# 5MMLedBreakoutForArduino.net
KiCad netlist of a schematic drawn in EAGLE
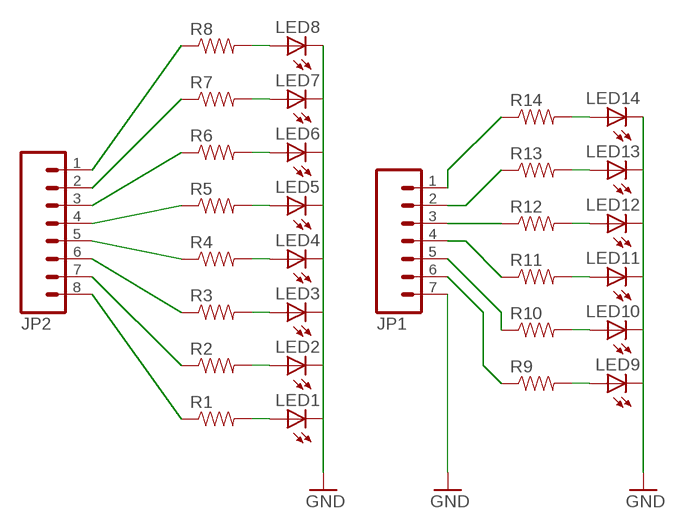
[diagram p0: schematic, sheet 1]

(export (version "E")
  (design (tool "Eeschema 10.0.6"))
  (components
    (comp (ref "JP1")
      (value "M07")
      (footprint "eagle-import:1X07")
      (libsource (lib "eagle-import") (part "M07"))
    )
    (comp (ref "JP2")
      (value "M081X08")
      (footprint "eagle-import:1X08")
      (libsource (lib "eagle-import") (part "M081X08"))
    )
    (comp (ref "LED1")
      (value "LED5MM")
      (footprint "eagle-import:LED5MM")
      (libsource (lib "eagle-import") (part "LED5MM"))
    )
    (comp (ref "LED2")
      (value "LED5MM")
      (footprint "eagle-import:LED5MM")
      (libsource (lib "eagle-import") (part "LED5MM"))
    )
    (comp (ref "LED3")
      (value "LED5MM")
      (footprint "eagle-import:LED5MM")
      (libsource (lib "eagle-import") (part "LED5MM"))
    )
    (comp (ref "LED4")
      (value "LED5MM")
      (footprint "eagle-import:LED5MM")
      (libsource (lib "eagle-import") (part "LED5MM"))
    )
    (comp (ref "LED5")
      (value "LED5MM")
      (footprint "eagle-import:LED5MM")
      (libsource (lib "eagle-import") (part "LED5MM"))
    )
    (comp (ref "LED6")
      (value "LED5MM")
      (footprint "eagle-import:LED5MM")
      (libsource (lib "eagle-import") (part "LED5MM"))
    )
    (comp (ref "LED7")
      (value "LED5MM")
      (footprint "eagle-import:LED5MM")
      (libsource (lib "eagle-import") (part "LED5MM"))
    )
    (comp (ref "LED8")
      (value "LED5MM")
      (footprint "eagle-import:LED5MM")
      (libsource (lib "eagle-import") (part "LED5MM"))
    )
    (comp (ref "LED9")
      (value "LED5MM")
      (footprint "eagle-import:LED5MM")
      (libsource (lib "eagle-import") (part "LED5MM"))
    )
    (comp (ref "LED10")
      (value "LED5MM")
      (footprint "eagle-import:LED5MM")
      (libsource (lib "eagle-import") (part "LED5MM"))
    )
    (comp (ref "LED11")
      (value "LED5MM")
      (footprint "eagle-import:LED5MM")
      (libsource (lib "eagle-import") (part "LED5MM"))
    )
    (comp (ref "LED12")
      (value "LED5MM")
      (footprint "eagle-import:LED5MM")
      (libsource (lib "eagle-import") (part "LED5MM"))
    )
    (comp (ref "LED13")
      (value "LED5MM")
      (footprint "eagle-import:LED5MM")
      (libsource (lib "eagle-import") (part "LED5MM"))
    )
    (comp (ref "LED14")
      (value "LED5MM")
      (footprint "eagle-import:LED5MM")
      (libsource (lib "eagle-import") (part "LED5MM"))
    )
    (comp (ref "R1")
      (value "RESISTORAXIAL-0.3")
      (footprint "eagle-import:AXIAL-0.3")
      (libsource (lib "eagle-import") (part "RESISTORAXIAL-0.3"))
    )
    (comp (ref "R2")
      (value "RESISTORAXIAL-0.3")
      (footprint "eagle-import:AXIAL-0.3")
      (libsource (lib "eagle-import") (part "RESISTORAXIAL-0.3"))
    )
    (comp (ref "R3")
      (value "RESISTORAXIAL-0.3")
      (footprint "eagle-import:AXIAL-0.3")
      (libsource (lib "eagle-import") (part "RESISTORAXIAL-0.3"))
    )
    (comp (ref "R4")
      (value "RESISTORAXIAL-0.3")
      (footprint "eagle-import:AXIAL-0.3")
      (libsource (lib "eagle-import") (part "RESISTORAXIAL-0.3"))
    )
    (comp (ref "R5")
      (value "RESISTORAXIAL-0.3")
      (footprint "eagle-import:AXIAL-0.3")
      (libsource (lib "eagle-import") (part "RESISTORAXIAL-0.3"))
    )
    (comp (ref "R6")
      (value "RESISTORAXIAL-0.3")
      (footprint "eagle-import:AXIAL-0.3")
      (libsource (lib "eagle-import") (part "RESISTORAXIAL-0.3"))
    )
    (comp (ref "R7")
      (value "RESISTORAXIAL-0.3")
      (footprint "eagle-import:AXIAL-0.3")
      (libsource (lib "eagle-import") (part "RESISTORAXIAL-0.3"))
    )
    (comp (ref "R8")
      (value "RESISTORAXIAL-0.3")
      (footprint "eagle-import:AXIAL-0.3")
      (libsource (lib "eagle-import") (part "RESISTORAXIAL-0.3"))
    )
    (comp (ref "R9")
      (value "RESISTORAXIAL-0.3")
      (footprint "eagle-import:AXIAL-0.3")
      (libsource (lib "eagle-import") (part "RESISTORAXIAL-0.3"))
    )
    (comp (ref "R10")
      (value "RESISTORAXIAL-0.3")
      (footprint "eagle-import:AXIAL-0.3")
      (libsource (lib "eagle-import") (part "RESISTORAXIAL-0.3"))
    )
    (comp (ref "R11")
      (value "RESISTORAXIAL-0.3")
      (footprint "eagle-import:AXIAL-0.3")
      (libsource (lib "eagle-import") (part "RESISTORAXIAL-0.3"))
    )
    (comp (ref "R12")
      (value "RESISTORAXIAL-0.3")
      (footprint "eagle-import:AXIAL-0.3")
      (libsource (lib "eagle-import") (part "RESISTORAXIAL-0.3"))
    )
    (comp (ref "R13")
      (value "RESISTORAXIAL-0.3")
      (footprint "eagle-import:AXIAL-0.3")
      (libsource (lib "eagle-import") (part "RESISTORAXIAL-0.3"))
    )
    (comp (ref "R14")
      (value "RESISTORAXIAL-0.3")
      (footprint "eagle-import:AXIAL-0.3")
      (libsource (lib "eagle-import") (part "RESISTORAXIAL-0.3"))
    )
  )
  (nets
    (net (code "1") (name "GND") (class "Default")
      (node (ref "JP1") (pin "7") (pinfunction "7_7") (pintype "passive"))
      (node (ref "LED1") (pin "K") (pinfunction "C_K") (pintype "passive"))
      (node (ref "LED10") (pin "K") (pinfunction "C_K") (pintype "passive"))
      (node (ref "LED11") (pin "K") (pinfunction "C_K") (pintype "passive"))
      (node (ref "LED12") (pin "K") (pinfunction "C_K") (pintype "passive"))
      (node (ref "LED13") (pin "K") (pinfunction "C_K") (pintype "passive"))
      (node (ref "LED14") (pin "K") (pinfunction "C_K") (pintype "passive"))
      (node (ref "LED2") (pin "K") (pinfunction "C_K") (pintype "passive"))
      (node (ref "LED3") (pin "K") (pinfunction "C_K") (pintype "passive"))
      (node (ref "LED4") (pin "K") (pinfunction "C_K") (pintype "passive"))
      (node (ref "LED5") (pin "K") (pinfunction "C_K") (pintype "passive"))
      (node (ref "LED6") (pin "K") (pinfunction "C_K") (pintype "passive"))
      (node (ref "LED7") (pin "K") (pinfunction "C_K") (pintype "passive"))
      (node (ref "LED8") (pin "K") (pinfunction "C_K") (pintype "passive"))
      (node (ref "LED9") (pin "K") (pinfunction "C_K") (pintype "passive"))
    )
    (net (code "2") (name "Net-(R1-1)") (class "Default")
      (node (ref "JP2") (pin "8") (pinfunction "8_8") (pintype "passive"))
      (node (ref "R1") (pin "P$1") (pinfunction "1_P$1") (pintype "passive"))
    )
    (net (code "3") (name "Net-(R1-2)") (class "Default")
      (node (ref "LED1") (pin "A") (pinfunction "A_A") (pintype "passive"))
      (node (ref "R1") (pin "P$2") (pinfunction "2_P$2") (pintype "passive"))
    )
    (net (code "4") (name "Net-(R2-1)") (class "Default")
      (node (ref "JP2") (pin "7") (pinfunction "7_7") (pintype "passive"))
      (node (ref "R2") (pin "P$1") (pinfunction "1_P$1") (pintype "passive"))
    )
    (net (code "5") (name "Net-(R2-2)") (class "Default")
      (node (ref "LED2") (pin "A") (pinfunction "A_A") (pintype "passive"))
      (node (ref "R2") (pin "P$2") (pinfunction "2_P$2") (pintype "passive"))
    )
    (net (code "6") (name "Net-(R3-1)") (class "Default")
      (node (ref "JP2") (pin "6") (pinfunction "6_6") (pintype "passive"))
      (node (ref "R3") (pin "P$1") (pinfunction "1_P$1") (pintype "passive"))
    )
    (net (code "7") (name "Net-(R3-2)") (class "Default")
      (node (ref "LED3") (pin "A") (pinfunction "A_A") (pintype "passive"))
      (node (ref "R3") (pin "P$2") (pinfunction "2_P$2") (pintype "passive"))
    )
    (net (code "8") (name "Net-(R4-1)") (class "Default")
      (node (ref "JP2") (pin "5") (pinfunction "5_5") (pintype "passive"))
      (node (ref "R4") (pin "P$1") (pinfunction "1_P$1") (pintype "passive"))
    )
    (net (code "9") (name "Net-(R4-2)") (class "Default")
      (node (ref "LED4") (pin "A") (pinfunction "A_A") (pintype "passive"))
      (node (ref "R4") (pin "P$2") (pinfunction "2_P$2") (pintype "passive"))
    )
    (net (code "10") (name "Net-(R5-1)") (class "Default")
      (node (ref "JP2") (pin "4") (pinfunction "4_4") (pintype "passive"))
      (node (ref "R5") (pin "P$1") (pinfunction "1_P$1") (pintype "passive"))
    )
    (net (code "11") (name "Net-(R5-2)") (class "Default")
      (node (ref "LED5") (pin "A") (pinfunction "A_A") (pintype "passive"))
      (node (ref "R5") (pin "P$2") (pinfunction "2_P$2") (pintype "passive"))
    )
    (net (code "12") (name "Net-(R6-1)") (class "Default")
      (node (ref "JP2") (pin "3") (pinfunction "3_3") (pintype "passive"))
      (node (ref "R6") (pin "P$1") (pinfunction "1_P$1") (pintype "passive"))
    )
    (net (code "13") (name "Net-(R6-2)") (class "Default")
      (node (ref "LED6") (pin "A") (pinfunction "A_A") (pintype "passive"))
      (node (ref "R6") (pin "P$2") (pinfunction "2_P$2") (pintype "passive"))
    )
    (net (code "14") (name "Net-(R7-1)") (class "Default")
      (node (ref "JP2") (pin "2") (pinfunction "2_2") (pintype "passive"))
      (node (ref "R7") (pin "P$1") (pinfunction "1_P$1") (pintype "passive"))
    )
    (net (code "15") (name "Net-(R7-2)") (class "Default")
      (node (ref "LED7") (pin "A") (pinfunction "A_A") (pintype "passive"))
      (node (ref "R7") (pin "P$2") (pinfunction "2_P$2") (pintype "passive"))
    )
    (net (code "16") (name "Net-(R8-1)") (class "Default")
      (node (ref "JP2") (pin "1") (pinfunction "1_1") (pintype "passive"))
      (node (ref "R8") (pin "P$1") (pinfunction "1_P$1") (pintype "passive"))
    )
    (net (code "17") (name "Net-(R8-2)") (class "Default")
      (node (ref "LED8") (pin "A") (pinfunction "A_A") (pintype "passive"))
      (node (ref "R8") (pin "P$2") (pinfunction "2_P$2") (pintype "passive"))
    )
    (net (code "18") (name "Net-(R9-1)") (class "Default")
      (node (ref "JP1") (pin "6") (pinfunction "6_6") (pintype "passive"))
      (node (ref "R9") (pin "P$1") (pinfunction "1_P$1") (pintype "passive"))
    )
    (net (code "19") (name "Net-(R9-2)") (class "Default")
      (node (ref "LED9") (pin "A") (pinfunction "A_A") (pintype "passive"))
      (node (ref "R9") (pin "P$2") (pinfunction "2_P$2") (pintype "passive"))
    )
    (net (code "20") (name "Net-(R10-1)") (class "Default")
      (node (ref "JP1") (pin "5") (pinfunction "5_5") (pintype "passive"))
      (node (ref "R10") (pin "P$1") (pinfunction "1_P$1") (pintype "passive"))
    )
    (net (code "21") (name "Net-(R10-2)") (class "Default")
      (node (ref "LED10") (pin "A") (pinfunction "A_A") (pintype "passive"))
      (node (ref "R10") (pin "P$2") (pinfunction "2_P$2") (pintype "passive"))
    )
    (net (code "22") (name "Net-(R11-1)") (class "Default")
      (node (ref "JP1") (pin "4") (pinfunction "4_4") (pintype "passive"))
      (node (ref "R11") (pin "P$1") (pinfunction "1_P$1") (pintype "passive"))
    )
    (net (code "23") (name "Net-(R11-2)") (class "Default")
      (node (ref "LED11") (pin "A") (pinfunction "A_A") (pintype "passive"))
      (node (ref "R11") (pin "P$2") (pinfunction "2_P$2") (pintype "passive"))
    )
    (net (code "24") (name "Net-(R12-1)") (class "Default")
      (node (ref "JP1") (pin "3") (pinfunction "3_3") (pintype "passive"))
      (node (ref "R12") (pin "P$1") (pinfunction "1_P$1") (pintype "passive"))
    )
    (net (code "25") (name "Net-(R12-2)") (class "Default")
      (node (ref "LED12") (pin "A") (pinfunction "A_A") (pintype "passive"))
      (node (ref "R12") (pin "P$2") (pinfunction "2_P$2") (pintype "passive"))
    )
    (net (code "26") (name "Net-(R13-1)") (class "Default")
      (node (ref "JP1") (pin "2") (pinfunction "2_2") (pintype "passive"))
      (node (ref "R13") (pin "P$1") (pinfunction "1_P$1") (pintype "passive"))
    )
    (net (code "27") (name "Net-(R13-2)") (class "Default")
      (node (ref "LED13") (pin "A") (pinfunction "A_A") (pintype "passive"))
      (node (ref "R13") (pin "P$2") (pinfunction "2_P$2") (pintype "passive"))
    )
    (net (code "28") (name "Net-(R14-1)") (class "Default")
      (node (ref "JP1") (pin "1") (pinfunction "1_1") (pintype "passive"))
      (node (ref "R14") (pin "P$1") (pinfunction "1_P$1") (pintype "passive"))
    )
    (net (code "29") (name "Net-(R14-2)") (class "Default")
      (node (ref "LED14") (pin "A") (pinfunction "A_A") (pintype "passive"))
      (node (ref "R14") (pin "P$2") (pinfunction "2_P$2") (pintype "passive"))
    )
  )
)
